# v21.net
KiCad netlist of a schematic drawn in EAGLE
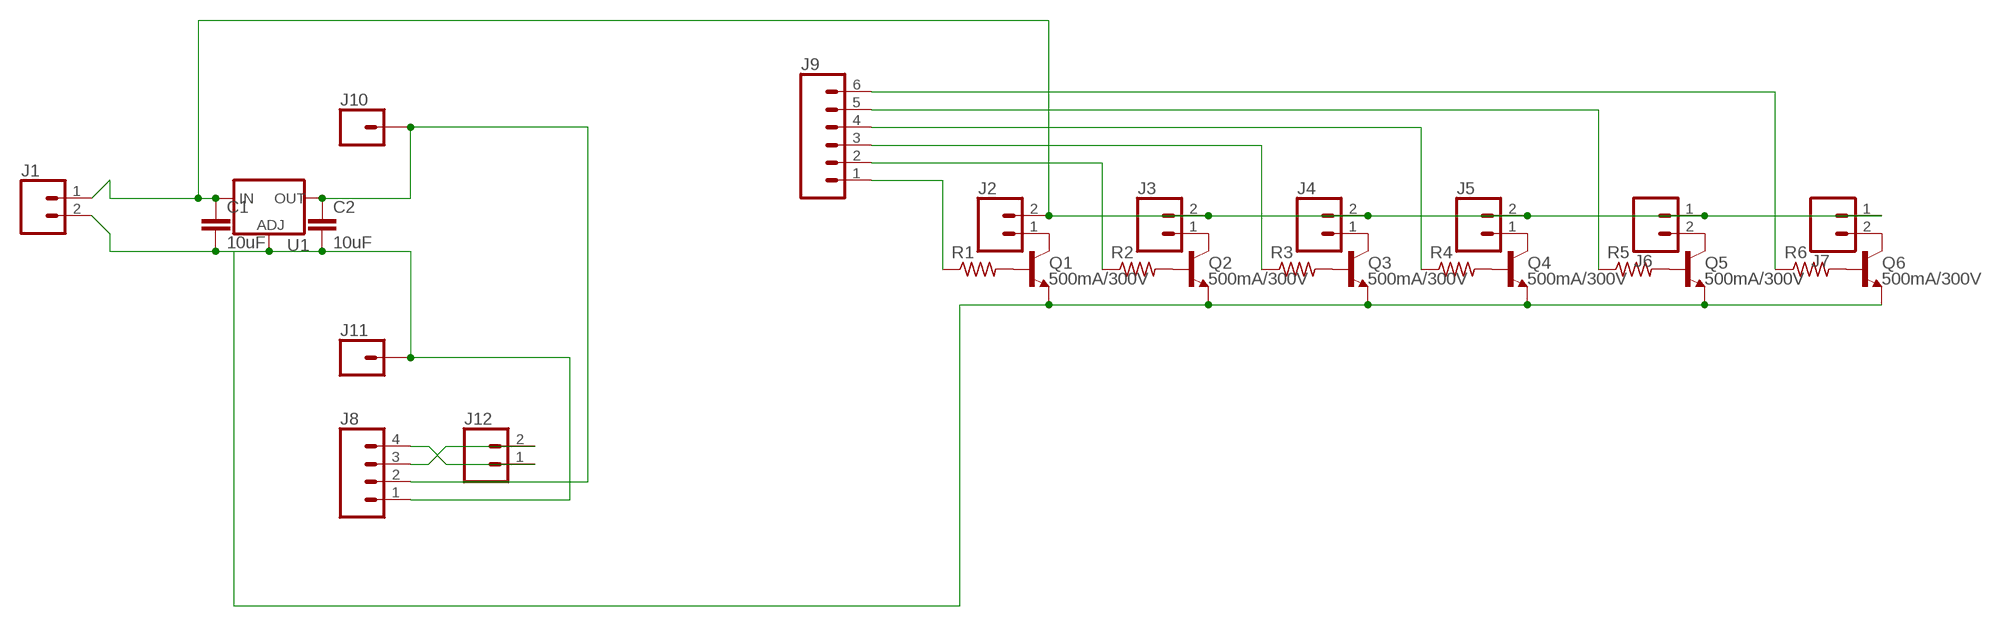
[diagram p0: schematic, sheet 1]

(export (version "E")
  (design (tool "Eeschema 10.0.6"))
  (components
    (comp (ref "C1")
      (value "10uF")
      (footprint "eagle-import:1206")
      (libsource (lib "eagle-import") (part "10UF-1206-6.3V-20%"))
    )
    (comp (ref "C2")
      (value "10uF")
      (footprint "eagle-import:1206")
      (libsource (lib "eagle-import") (part "10UF-1206-6.3V-20%"))
    )
    (comp (ref "J1")
      (value "CONN_02-JST-2MM-SMT")
      (footprint "eagle-import:JST-2-SMD")
      (libsource (lib "eagle-import") (part "CONN_02-JST-2MM-SMT"))
    )
    (comp (ref "J2")
      (value "CONN_02")
      (footprint "eagle-import:1X02")
      (libsource (lib "eagle-import") (part "CONN_02"))
    )
    (comp (ref "J3")
      (value "CONN_02")
      (footprint "eagle-import:1X02")
      (libsource (lib "eagle-import") (part "CONN_02"))
    )
    (comp (ref "J4")
      (value "CONN_02")
      (footprint "eagle-import:1X02")
      (libsource (lib "eagle-import") (part "CONN_02"))
    )
    (comp (ref "J5")
      (value "CONN_02")
      (footprint "eagle-import:1X02")
      (libsource (lib "eagle-import") (part "CONN_02"))
    )
    (comp (ref "J6")
      (value "CONN_02")
      (footprint "eagle-import:1X02")
      (libsource (lib "eagle-import") (part "CONN_02"))
    )
    (comp (ref "J7")
      (value "CONN_02")
      (footprint "eagle-import:1X02")
      (libsource (lib "eagle-import") (part "CONN_02"))
    )
    (comp (ref "J8")
      (value "CONN_04PTH")
      (footprint "eagle-import:1X04")
      (libsource (lib "eagle-import") (part "CONN_04PTH"))
    )
    (comp (ref "J9")
      (value "CONN_06LONGPADS")
      (footprint "eagle-import:1X06_LONGPADS")
      (libsource (lib "eagle-import") (part "CONN_06LONGPADS"))
    )
    (comp (ref "J10")
      (value "CONN_01PTH_LONGPAD")
      (footprint "eagle-import:1X01_LONGPAD")
      (libsource (lib "eagle-import") (part "CONN_01PTH_LONGPAD"))
    )
    (comp (ref "J11")
      (value "CONN_01PTH_LONGPAD")
      (footprint "eagle-import:1X01_LONGPAD")
      (libsource (lib "eagle-import") (part "CONN_01PTH_LONGPAD"))
    )
    (comp (ref "J12")
      (value "CONN_02LOCK_LONGPADS")
      (footprint "eagle-import:1X02_LOCK_LONGPADS")
      (libsource (lib "eagle-import") (part "CONN_02LOCK_LONGPADS"))
    )
    (comp (ref "Q1")
      (value "500mA/300V")
      (footprint "eagle-import:SOT23-3")
      (libsource (lib "eagle-import") (part "TRANS_NPN-MMBTA42"))
    )
    (comp (ref "Q2")
      (value "500mA/300V")
      (footprint "eagle-import:SOT23-3")
      (libsource (lib "eagle-import") (part "TRANS_NPN-MMBTA42"))
    )
    (comp (ref "Q3")
      (value "500mA/300V")
      (footprint "eagle-import:SOT23-3")
      (libsource (lib "eagle-import") (part "TRANS_NPN-MMBTA42"))
    )
    (comp (ref "Q4")
      (value "500mA/300V")
      (footprint "eagle-import:SOT23-3")
      (libsource (lib "eagle-import") (part "TRANS_NPN-MMBTA42"))
    )
    (comp (ref "Q5")
      (value "500mA/300V")
      (footprint "eagle-import:SOT23-3")
      (libsource (lib "eagle-import") (part "TRANS_NPN-MMBTA42"))
    )
    (comp (ref "Q6")
      (value "500mA/300V")
      (footprint "eagle-import:SOT23-3")
      (libsource (lib "eagle-import") (part "TRANS_NPN-MMBTA42"))
    )
    (comp (ref "R1")
      (value "R-US_R1206")
      (footprint "eagle-import:R1206")
      (libsource (lib "eagle-import") (part "R-US_R1206"))
    )
    (comp (ref "R2")
      (value "R-US_R1206")
      (footprint "eagle-import:R1206")
      (libsource (lib "eagle-import") (part "R-US_R1206"))
    )
    (comp (ref "R3")
      (value "R-US_R1206")
      (footprint "eagle-import:R1206")
      (libsource (lib "eagle-import") (part "R-US_R1206"))
    )
    (comp (ref "R4")
      (value "R-US_R1206")
      (footprint "eagle-import:R1206")
      (libsource (lib "eagle-import") (part "R-US_R1206"))
    )
    (comp (ref "R5")
      (value "R-US_R1206")
      (footprint "eagle-import:R1206")
      (libsource (lib "eagle-import") (part "R-US_R1206"))
    )
    (comp (ref "R6")
      (value "R-US_R1206")
      (footprint "eagle-import:R1206")
      (libsource (lib "eagle-import") (part "R-US_R1206"))
    )
    (comp (ref "U1")
      (value "V_REG_LM1117SOT223")
      (footprint "eagle-import:SOT223")
      (libsource (lib "eagle-import") (part "V_REG_LM1117SOT223"))
    )
  )
  (nets
    (net (code "1") (name "Net-(C2-Pad1)") (class "Default")
      (node (ref "C2") (pin "1") (pinfunction "1_1") (pintype "passive"))
      (node (ref "J10") (pin "1") (pinfunction "1_1") (pintype "passive"))
      (node (ref "J8") (pin "2") (pinfunction "2_2") (pintype "passive"))
      (node (ref "U1") (pin "2") (pinfunction "OUT_2") (pintype "output"))
      (node (ref "U1") (pin "4") (pinfunction "OUT_4") (pintype "output"))
    )
    (net (code "2") (name "Net-(J1-1)") (class "Default")
      (node (ref "C1") (pin "2") (pinfunction "2_2") (pintype "passive"))
      (node (ref "C2") (pin "2") (pinfunction "2_2") (pintype "passive"))
      (node (ref "J1") (pin "2") (pinfunction "1_2") (pintype "passive"))
      (node (ref "J11") (pin "1") (pinfunction "1_1") (pintype "passive"))
      (node (ref "J8") (pin "1") (pinfunction "1_1") (pintype "passive"))
      (node (ref "Q1") (pin "2") (pinfunction "E_2") (pintype "passive"))
      (node (ref "Q2") (pin "2") (pinfunction "E_2") (pintype "passive"))
      (node (ref "Q3") (pin "2") (pinfunction "E_2") (pintype "passive"))
      (node (ref "Q4") (pin "2") (pinfunction "E_2") (pintype "passive"))
      (node (ref "Q5") (pin "2") (pinfunction "E_2") (pintype "passive"))
      (node (ref "Q6") (pin "2") (pinfunction "E_2") (pintype "passive"))
      (node (ref "U1") (pin "1") (pinfunction "ADJ_1") (pintype "input"))
    )
    (net (code "3") (name "Net-(J1-2)") (class "Default")
      (node (ref "C1") (pin "1") (pinfunction "1_1") (pintype "passive"))
      (node (ref "J1") (pin "1") (pinfunction "2_1") (pintype "passive"))
      (node (ref "J2") (pin "2") (pinfunction "2_2") (pintype "passive"))
      (node (ref "J3") (pin "2") (pinfunction "2_2") (pintype "passive"))
      (node (ref "J4") (pin "2") (pinfunction "2_2") (pintype "passive"))
      (node (ref "J5") (pin "2") (pinfunction "2_2") (pintype "passive"))
      (node (ref "J6") (pin "1") (pinfunction "1_1") (pintype "passive"))
      (node (ref "J7") (pin "1") (pinfunction "1_1") (pintype "passive"))
      (node (ref "U1") (pin "3") (pinfunction "IN_3") (pintype "input"))
    )
    (net (code "4") (name "Net-(J9-Pad1)") (class "Default")
      (node (ref "J9") (pin "1") (pinfunction "1_1") (pintype "passive"))
      (node (ref "R1") (pin "1") (pinfunction "1_1") (pintype "passive"))
    )
    (net (code "5") (name "Net-(J9-Pad2)") (class "Default")
      (node (ref "J9") (pin "2") (pinfunction "2_2") (pintype "passive"))
      (node (ref "R2") (pin "1") (pinfunction "1_1") (pintype "passive"))
    )
    (net (code "6") (name "Net-(J9-Pad3)") (class "Default")
      (node (ref "J9") (pin "3") (pinfunction "3_3") (pintype "passive"))
      (node (ref "R3") (pin "1") (pinfunction "1_1") (pintype "passive"))
    )
    (net (code "7") (name "Net-(J9-Pad4)") (class "Default")
      (node (ref "J9") (pin "4") (pinfunction "4_4") (pintype "passive"))
      (node (ref "R4") (pin "1") (pinfunction "1_1") (pintype "passive"))
    )
    (net (code "8") (name "Net-(J9-Pad5)") (class "Default")
      (node (ref "J9") (pin "5") (pinfunction "5_5") (pintype "passive"))
      (node (ref "R5") (pin "1") (pinfunction "1_1") (pintype "passive"))
    )
    (net (code "9") (name "Net-(J9-Pad6)") (class "Default")
      (node (ref "J9") (pin "6") (pinfunction "6_6") (pintype "passive"))
      (node (ref "R6") (pin "1") (pinfunction "1_1") (pintype "passive"))
    )
    (net (code "10") (name "Net-(J12-Pad1)") (class "Default")
      (node (ref "J12") (pin "1") (pinfunction "1_1") (pintype "passive"))
      (node (ref "J8") (pin "4") (pinfunction "4_4") (pintype "passive"))
    )
    (net (code "11") (name "Net-(J12-Pad2)") (class "Default")
      (node (ref "J12") (pin "2") (pinfunction "2_2") (pintype "passive"))
      (node (ref "J8") (pin "3") (pinfunction "3_3") (pintype "passive"))
    )
    (net (code "12") (name "Net-(Q1-B)") (class "Default")
      (node (ref "Q1") (pin "1") (pinfunction "B_1") (pintype "passive"))
      (node (ref "R1") (pin "2") (pinfunction "2_2") (pintype "passive"))
    )
    (net (code "13") (name "Net-(Q1-C)") (class "Default")
      (node (ref "J2") (pin "1") (pinfunction "1_1") (pintype "passive"))
      (node (ref "Q1") (pin "3") (pinfunction "C_3") (pintype "passive"))
    )
    (net (code "14") (name "Net-(Q2-B)") (class "Default")
      (node (ref "Q2") (pin "1") (pinfunction "B_1") (pintype "passive"))
      (node (ref "R2") (pin "2") (pinfunction "2_2") (pintype "passive"))
    )
    (net (code "15") (name "Net-(Q2-C)") (class "Default")
      (node (ref "J3") (pin "1") (pinfunction "1_1") (pintype "passive"))
      (node (ref "Q2") (pin "3") (pinfunction "C_3") (pintype "passive"))
    )
    (net (code "16") (name "Net-(Q3-B)") (class "Default")
      (node (ref "Q3") (pin "1") (pinfunction "B_1") (pintype "passive"))
      (node (ref "R3") (pin "2") (pinfunction "2_2") (pintype "passive"))
    )
    (net (code "17") (name "Net-(Q3-C)") (class "Default")
      (node (ref "J4") (pin "1") (pinfunction "1_1") (pintype "passive"))
      (node (ref "Q3") (pin "3") (pinfunction "C_3") (pintype "passive"))
    )
    (net (code "18") (name "Net-(Q4-B)") (class "Default")
      (node (ref "Q4") (pin "1") (pinfunction "B_1") (pintype "passive"))
      (node (ref "R4") (pin "2") (pinfunction "2_2") (pintype "passive"))
    )
    (net (code "19") (name "Net-(Q4-C)") (class "Default")
      (node (ref "J5") (pin "1") (pinfunction "1_1") (pintype "passive"))
      (node (ref "Q4") (pin "3") (pinfunction "C_3") (pintype "passive"))
    )
    (net (code "20") (name "Net-(Q5-B)") (class "Default")
      (node (ref "Q5") (pin "1") (pinfunction "B_1") (pintype "passive"))
      (node (ref "R5") (pin "2") (pinfunction "2_2") (pintype "passive"))
    )
    (net (code "21") (name "Net-(Q5-C)") (class "Default")
      (node (ref "J6") (pin "2") (pinfunction "2_2") (pintype "passive"))
      (node (ref "Q5") (pin "3") (pinfunction "C_3") (pintype "passive"))
    )
    (net (code "22") (name "Net-(Q6-B)") (class "Default")
      (node (ref "Q6") (pin "1") (pinfunction "B_1") (pintype "passive"))
      (node (ref "R6") (pin "2") (pinfunction "2_2") (pintype "passive"))
    )
    (net (code "23") (name "Net-(Q6-C)") (class "Default")
      (node (ref "J7") (pin "2") (pinfunction "2_2") (pintype "passive"))
      (node (ref "Q6") (pin "3") (pinfunction "C_3") (pintype "passive"))
    )
  )
)
